# v2_power_board.net
KiCad netlist of a schematic drawn in EAGLE
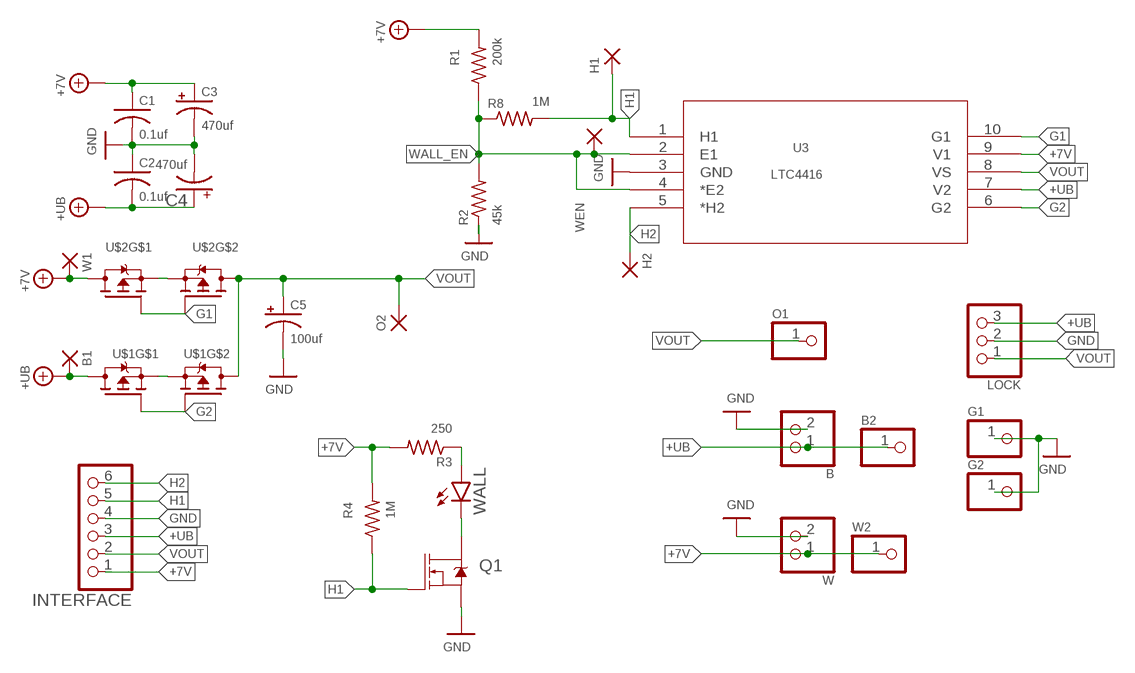
[diagram p0: schematic, sheet 1]

(export (version "E")
  (design (tool "Eeschema 10.0.6"))
  (components
    (comp (ref "B")
      (value "PINHD-1X2")
      (footprint "eagle-import:1X02")
      (libsource (lib "eagle-import") (part "PINHD-1X2"))
    )
    (comp (ref "B1")
      (value "SMD2")
      (footprint "eagle-import:SMD1,27-2,54")
      (libsource (lib "eagle-import") (part "SMD2"))
    )
    (comp (ref "B2")
      (value "PINHD-1X1")
      (footprint "eagle-import:1X01")
      (libsource (lib "eagle-import") (part "PINHD-1X1"))
    )
    (comp (ref "C1")
      (value "0.1uf")
      (footprint "eagle-import:C0805")
      (libsource (lib "eagle-import") (part "C-USC0805"))
    )
    (comp (ref "C2")
      (value "0.1uf")
      (footprint "eagle-import:C0805")
      (libsource (lib "eagle-import") (part "C-USC0805"))
    )
    (comp (ref "C3")
      (value "470uf")
      (footprint "eagle-import:140CLH-0810")
      (libsource (lib "eagle-import") (part "CPOL-US140CLH-0810"))
    )
    (comp (ref "C4")
      (value "470uf")
      (footprint "eagle-import:140CLH-0810")
      (libsource (lib "eagle-import") (part "CPOL-US140CLH-0810"))
    )
    (comp (ref "C5")
      (value "100uf")
      (footprint "eagle-import:140CLH-0810")
      (libsource (lib "eagle-import") (part "CPOL-US140CLH-0810"))
    )
    (comp (ref "G1")
      (value "PINHD-1X1")
      (footprint "eagle-import:1X01")
      (libsource (lib "eagle-import") (part "PINHD-1X1"))
    )
    (comp (ref "G2")
      (value "PINHD-1X1")
      (footprint "eagle-import:1X01")
      (libsource (lib "eagle-import") (part "PINHD-1X1"))
    )
    (comp (ref "H1")
      (value "SMD2")
      (footprint "eagle-import:SMD1,27-2,54")
      (libsource (lib "eagle-import") (part "SMD2"))
    )
    (comp (ref "H2")
      (value "SMD2")
      (footprint "eagle-import:SMD1,27-2,54")
      (libsource (lib "eagle-import") (part "SMD2"))
    )
    (comp (ref "INTERFACE")
      (value "PINHD-1X6")
      (footprint "eagle-import:1X06")
      (libsource (lib "eagle-import") (part "PINHD-1X6"))
    )
    (comp (ref "LOCK")
      (value "PINHD-1X3")
      (footprint "eagle-import:1X03")
      (libsource (lib "eagle-import") (part "PINHD-1X3"))
    )
    (comp (ref "O1")
      (value "PINHD-1X1")
      (footprint "eagle-import:1X01")
      (libsource (lib "eagle-import") (part "PINHD-1X1"))
    )
    (comp (ref "O2")
      (value "SMD2")
      (footprint "eagle-import:SMD1,27-2,54")
      (libsource (lib "eagle-import") (part "SMD2"))
    )
    (comp (ref "Q1")
      (value "310mA/60V/1.6Ω")
      (footprint "eagle-import:SOT323")
      (libsource (lib "eagle-import") (part "MOSFET-NCH-2N7002PW"))
    )
    (comp (ref "R1")
      (value "200k")
      (footprint "eagle-import:R0805")
      (libsource (lib "eagle-import") (part "R-US_R0805"))
    )
    (comp (ref "R2")
      (value "45k")
      (footprint "eagle-import:R0805")
      (libsource (lib "eagle-import") (part "R-US_R0805"))
    )
    (comp (ref "R3")
      (value "250")
      (footprint "eagle-import:R0805")
      (libsource (lib "eagle-import") (part "R-US_R0805"))
    )
    (comp (ref "R4")
      (value "1M")
      (footprint "eagle-import:R0805")
      (libsource (lib "eagle-import") (part "R-US_R0805"))
    )
    (comp (ref "R8")
      (value "1M")
      (footprint "eagle-import:R0805")
      (libsource (lib "eagle-import") (part "R-US_R0805"))
    )
    (comp (ref "U$1")
      (value "IRF7314PBF")
      (footprint "eagle-import:SO-8")
      (fields (field (name "MF") "Infineon"))
      (libsource (lib "eagle-import") (part "IRF7314PBF"))
    )
    (comp (ref "U$2")
      (value "IRF7314PBF")
      (footprint "eagle-import:SO-8")
      (fields (field (name "MF") "Infineon"))
      (libsource (lib "eagle-import") (part "IRF7314PBF"))
    )
    (comp (ref "U3")
      (value "LTC4416")
      (footprint "eagle-import:MSOP-10_MS")
      (fields (field (name "MF") "Analog Devices") (field (name "MP") "LTC4416IMS#PBF"))
      (libsource (lib "eagle-import") (part "LTC4416IMS#PBF"))
    )
    (comp (ref "W")
      (value "PINHD-1X2")
      (footprint "eagle-import:1X02")
      (libsource (lib "eagle-import") (part "PINHD-1X2"))
    )
    (comp (ref "W1")
      (value "SMD2")
      (footprint "eagle-import:SMD1,27-2,54")
      (libsource (lib "eagle-import") (part "SMD2"))
    )
    (comp (ref "W2")
      (value "PINHD-1X1")
      (footprint "eagle-import:1X01")
      (libsource (lib "eagle-import") (part "PINHD-1X1"))
    )
    (comp (ref "WALL")
      (value "LEDSML0805")
      (footprint "eagle-import:SML0805")
      (libsource (lib "eagle-import") (part "LEDSML0805"))
    )
    (comp (ref "WEN")
      (value "SMD2")
      (footprint "eagle-import:SMD1,27-2,54")
      (libsource (lib "eagle-import") (part "SMD2"))
    )
  )
  (nets
    (net (code "1") (name "+7V") (class "Default")
      (node (ref "C1") (pin "1") (pinfunction "1_1") (pintype "passive"))
      (node (ref "C3") (pin "+") (pinfunction "+_+") (pintype "passive"))
      (node (ref "INTERFACE") (pin "1") (pinfunction "1_1") (pintype "passive"))
      (node (ref "R1") (pin "2") (pinfunction "2_2") (pintype "passive"))
      (node (ref "R3") (pin "2") (pinfunction "2_2") (pintype "passive"))
      (node (ref "R4") (pin "2") (pinfunction "2_2") (pintype "passive"))
      (node (ref "U$2") (pin "7") (pinfunction "D_7") (pintype "passive"))
      (node (ref "U$2") (pin "8") (pinfunction "D_8") (pintype "passive"))
      (node (ref "U3") (pin "9") (pinfunction "V1_9") (pintype "input"))
      (node (ref "W") (pin "1") (pinfunction "1_1") (pintype "passive"))
      (node (ref "W1") (pin "1") (pinfunction "P_1") (pintype "passive"))
      (node (ref "W2") (pin "1") (pinfunction "1_1") (pintype "passive"))
    )
    (net (code "2") (name "+UB") (class "Default")
      (node (ref "B") (pin "1") (pinfunction "1_1") (pintype "passive"))
      (node (ref "B1") (pin "1") (pinfunction "P_1") (pintype "passive"))
      (node (ref "B2") (pin "1") (pinfunction "1_1") (pintype "passive"))
      (node (ref "C2") (pin "2") (pinfunction "2_2") (pintype "passive"))
      (node (ref "C4") (pin "+") (pinfunction "+_+") (pintype "passive"))
      (node (ref "INTERFACE") (pin "3") (pinfunction "3_3") (pintype "passive"))
      (node (ref "LOCK") (pin "3") (pinfunction "3_3") (pintype "passive"))
      (node (ref "U$1") (pin "7") (pinfunction "D_7") (pintype "passive"))
      (node (ref "U$1") (pin "8") (pinfunction "D_8") (pintype "passive"))
      (node (ref "U3") (pin "7") (pinfunction "V2_7") (pintype "input"))
    )
    (net (code "3") (name "G1") (class "Default")
      (node (ref "U$2") (pin "2") (pinfunction "G_2") (pintype "passive"))
      (node (ref "U$2") (pin "4") (pinfunction "G_4") (pintype "passive"))
      (node (ref "U3") (pin "10") (pinfunction "G1_10") (pintype "passive"))
    )
    (net (code "4") (name "G2") (class "Default")
      (node (ref "U$1") (pin "2") (pinfunction "G_2") (pintype "passive"))
      (node (ref "U$1") (pin "4") (pinfunction "G_4") (pintype "passive"))
      (node (ref "U3") (pin "6") (pinfunction "G2_6") (pintype "passive"))
    )
    (net (code "5") (name "GND") (class "Default")
      (node (ref "B") (pin "2") (pinfunction "2_2") (pintype "passive"))
      (node (ref "C1") (pin "2") (pinfunction "2_2") (pintype "passive"))
      (node (ref "C2") (pin "1") (pinfunction "1_1") (pintype "passive"))
      (node (ref "C3") (pin "-") (pinfunction "-_-") (pintype "passive"))
      (node (ref "C4") (pin "-") (pinfunction "-_-") (pintype "passive"))
      (node (ref "C5") (pin "-") (pinfunction "-_-") (pintype "passive"))
      (node (ref "G1") (pin "1") (pinfunction "1_1") (pintype "passive"))
      (node (ref "G2") (pin "1") (pinfunction "1_1") (pintype "passive"))
      (node (ref "INTERFACE") (pin "4") (pinfunction "4_4") (pintype "passive"))
      (node (ref "LOCK") (pin "2") (pinfunction "2_2") (pintype "passive"))
      (node (ref "Q1") (pin "2") (pinfunction "S_2") (pintype "bidirectional"))
      (node (ref "R2") (pin "1") (pinfunction "1_1") (pintype "passive"))
      (node (ref "U3") (pin "3") (pinfunction "GND_3") (pintype "power_in"))
      (node (ref "W") (pin "2") (pinfunction "2_2") (pintype "passive"))
    )
    (net (code "6") (name "H1") (class "Default")
      (node (ref "H1") (pin "1") (pinfunction "P_1") (pintype "passive"))
      (node (ref "INTERFACE") (pin "5") (pinfunction "5_5") (pintype "passive"))
      (node (ref "Q1") (pin "1") (pinfunction "G_1") (pintype "bidirectional"))
      (node (ref "R4") (pin "1") (pinfunction "1_1") (pintype "passive"))
      (node (ref "R8") (pin "2") (pinfunction "2_2") (pintype "passive"))
      (node (ref "U3") (pin "1") (pinfunction "H1_1") (pintype "output"))
    )
    (net (code "7") (name "H2") (class "Default")
      (node (ref "H2") (pin "1") (pinfunction "P_1") (pintype "passive"))
      (node (ref "INTERFACE") (pin "6") (pinfunction "6_6") (pintype "passive"))
      (node (ref "U3") (pin "5") (pinfunction "*H2_5") (pintype "input"))
    )
    (net (code "8") (name "Net-(Q1-D)") (class "Default")
      (node (ref "Q1") (pin "3") (pinfunction "D_3") (pintype "bidirectional"))
      (node (ref "WALL") (pin "C") (pinfunction "C_C") (pintype "passive"))
    )
    (net (code "9") (name "Net-(R3-Pad1)") (class "Default")
      (node (ref "R3") (pin "1") (pinfunction "1_1") (pintype "passive"))
      (node (ref "WALL") (pin "A") (pinfunction "A_A") (pintype "passive"))
    )
    (net (code "10") (name "Net-(U$1A-S)") (class "Default")
      (node (ref "U$1") (pin "1") (pinfunction "S_1") (pintype "passive"))
      (node (ref "U$1") (pin "3") (pinfunction "S_3") (pintype "passive"))
    )
    (net (code "11") (name "Net-(U$2A-S)") (class "Default")
      (node (ref "U$2") (pin "1") (pinfunction "S_1") (pintype "passive"))
      (node (ref "U$2") (pin "3") (pinfunction "S_3") (pintype "passive"))
    )
    (net (code "12") (name "VOUT") (class "Default")
      (node (ref "C5") (pin "+") (pinfunction "+_+") (pintype "passive"))
      (node (ref "INTERFACE") (pin "2") (pinfunction "2_2") (pintype "passive"))
      (node (ref "LOCK") (pin "1") (pinfunction "1_1") (pintype "passive"))
      (node (ref "O1") (pin "1") (pinfunction "1_1") (pintype "passive"))
      (node (ref "O2") (pin "1") (pinfunction "P_1") (pintype "passive"))
      (node (ref "U$1") (pin "5") (pinfunction "D_5") (pintype "passive"))
      (node (ref "U$1") (pin "6") (pinfunction "D_6") (pintype "passive"))
      (node (ref "U$2") (pin "5") (pinfunction "D_5") (pintype "passive"))
      (node (ref "U$2") (pin "6") (pinfunction "D_6") (pintype "passive"))
      (node (ref "U3") (pin "8") (pinfunction "VS_8") (pintype "input"))
    )
    (net (code "13") (name "WALL_EN") (class "Default")
      (node (ref "R1") (pin "1") (pinfunction "1_1") (pintype "passive"))
      (node (ref "R2") (pin "2") (pinfunction "2_2") (pintype "passive"))
      (node (ref "R8") (pin "1") (pinfunction "1_1") (pintype "passive"))
      (node (ref "U3") (pin "2") (pinfunction "E1_2") (pintype "input"))
      (node (ref "U3") (pin "4") (pinfunction "*E2_4") (pintype "input"))
      (node (ref "WEN") (pin "1") (pinfunction "P_1") (pintype "passive"))
    )
  )
)
